# RPIShield.net
KiCad netlist of a schematic drawn in Altium Designer
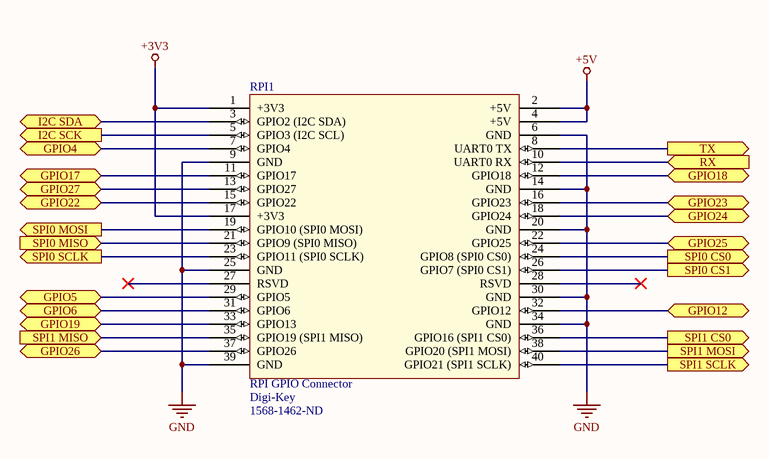
[diagram p0: RPIShield.SchDoc]

(export (version "E")
  (design (tool "Eeschema 10.0.6"))
  (components
    (comp (ref "RPI1")
      (value "RPI GPIO Connector")
      (footprint "rpi")
      (description "GPIO Header for Raspberry Pi A+/B+/Pi 2/Pi 3 - 2x20")
      (fields
        (field (name "MANUFACTURER") "SparkFun Electronics")
        (field (name "MANUFACTURER PART NUMBER") "PRT-14017")
        (field (name "SUPPLIER 1") "Digi-Key")
        (field (name "SUPPLIER PART NUMBER 1") "1568-1462-ND")
      )
      (libsource (lib "rpi") (part "rpi connector"))
    )
  )
  (nets
    (net (code "1") (name "+3V3") (class "Default")
      (node (ref "RPI1") (pin "1") (pinfunction "+3V3_1") (pintype "power_in"))
      (node (ref "RPI1") (pin "17") (pinfunction "+3V3_17") (pintype "power_in"))
    )
    (net (code "2") (name "+5V") (class "Default")
      (node (ref "RPI1") (pin "2") (pinfunction "+5V_2") (pintype "power_in"))
      (node (ref "RPI1") (pin "4") (pinfunction "+5V_4") (pintype "power_in"))
    )
    (net (code "3") (name "/GPIO4") (class "Default")
      (node (ref "RPI1") (pin "7") (pinfunction "GPIO4_7") (pintype "bidirectional"))
    )
    (net (code "4") (name "/GPIO5") (class "Default")
      (node (ref "RPI1") (pin "29") (pinfunction "GPIO5_29") (pintype "bidirectional"))
    )
    (net (code "5") (name "/GPIO6") (class "Default")
      (node (ref "RPI1") (pin "31") (pinfunction "GPIO6_31") (pintype "bidirectional"))
    )
    (net (code "6") (name "/GPIO12") (class "Default")
      (node (ref "RPI1") (pin "32") (pinfunction "GPIO12_32") (pintype "bidirectional"))
    )
    (net (code "7") (name "/GPIO17") (class "Default")
      (node (ref "RPI1") (pin "11") (pinfunction "GPIO17_11") (pintype "bidirectional"))
    )
    (net (code "8") (name "/GPIO18") (class "Default")
      (node (ref "RPI1") (pin "12") (pinfunction "GPIO18_12") (pintype "bidirectional"))
    )
    (net (code "9") (name "/GPIO19") (class "Default")
      (node (ref "RPI1") (pin "33") (pinfunction "GPIO13_33") (pintype "bidirectional"))
    )
    (net (code "10") (name "/GPIO22") (class "Default")
      (node (ref "RPI1") (pin "15") (pinfunction "GPIO22_15") (pintype "bidirectional"))
    )
    (net (code "11") (name "/GPIO23") (class "Default")
      (node (ref "RPI1") (pin "16") (pinfunction "GPIO23_16") (pintype "bidirectional"))
    )
    (net (code "12") (name "/GPIO24") (class "Default")
      (node (ref "RPI1") (pin "18") (pinfunction "GPIO24_18") (pintype "bidirectional"))
    )
    (net (code "13") (name "/GPIO25") (class "Default")
      (node (ref "RPI1") (pin "22") (pinfunction "GPIO25_22") (pintype "bidirectional"))
    )
    (net (code "14") (name "/GPIO26") (class "Default")
      (node (ref "RPI1") (pin "37") (pinfunction "GPIO26_37") (pintype "bidirectional"))
    )
    (net (code "15") (name "/GPIO27") (class "Default")
      (node (ref "RPI1") (pin "13") (pinfunction "GPIO27_13") (pintype "bidirectional"))
    )
    (net (code "16") (name "/I2C SCK") (class "Default")
      (node (ref "RPI1") (pin "5") (pinfunction "GPIO3_(I2C_SCL)_5") (pintype "bidirectional"))
    )
    (net (code "17") (name "/I2C SDA") (class "Default")
      (node (ref "RPI1") (pin "3") (pinfunction "GPIO2_(I2C_SDA)_3") (pintype "bidirectional"))
    )
    (net (code "18") (name "/RX") (class "Default")
      (node (ref "RPI1") (pin "10") (pinfunction "UART0_RX_10") (pintype "bidirectional"))
    )
    (net (code "19") (name "/SPI0 CS0") (class "Default")
      (node (ref "RPI1") (pin "24") (pinfunction "GPIO8_(SPI0_CS0)_24") (pintype "bidirectional"))
    )
    (net (code "20") (name "/SPI0 CS1") (class "Default")
      (node (ref "RPI1") (pin "26") (pinfunction "GPIO7_(SPI0_CS1)_26") (pintype "bidirectional"))
    )
    (net (code "21") (name "/SPI0 MISO") (class "Default")
      (node (ref "RPI1") (pin "21") (pinfunction "GPIO9_(SPI0_MISO)_21") (pintype "bidirectional"))
    )
    (net (code "22") (name "/SPI0 MOSI") (class "Default")
      (node (ref "RPI1") (pin "19") (pinfunction "GPIO10_(SPI0_MOSI)_19") (pintype "bidirectional"))
    )
    (net (code "23") (name "/SPI0 SCLK") (class "Default")
      (node (ref "RPI1") (pin "23") (pinfunction "GPIO11_(SPI0_SCLK)_23") (pintype "bidirectional"))
    )
    (net (code "24") (name "/SPI1 CS0") (class "Default")
      (node (ref "RPI1") (pin "36") (pinfunction "GPIO16_(SPI1_CS0)_36") (pintype "bidirectional"))
    )
    (net (code "25") (name "/SPI1 MISO") (class "Default")
      (node (ref "RPI1") (pin "35") (pinfunction "GPIO19_(SPI1_MISO)_35") (pintype "bidirectional"))
    )
    (net (code "26") (name "/SPI1 MOSI") (class "Default")
      (node (ref "RPI1") (pin "38") (pinfunction "GPIO20_(SPI1_MOSI)_38") (pintype "bidirectional"))
    )
    (net (code "27") (name "/SPI1 SCLK") (class "Default")
      (node (ref "RPI1") (pin "40") (pinfunction "GPIO21_(SPI1_SCLK)_40") (pintype "bidirectional"))
    )
    (net (code "28") (name "/TX") (class "Default")
      (node (ref "RPI1") (pin "8") (pinfunction "UART0_TX_8") (pintype "bidirectional"))
    )
    (net (code "29") (name "GND") (class "Default")
      (node (ref "RPI1") (pin "14") (pinfunction "GND_14") (pintype "power_in"))
      (node (ref "RPI1") (pin "20") (pinfunction "GND_20") (pintype "power_in"))
      (node (ref "RPI1") (pin "25") (pinfunction "GND_25") (pintype "power_in"))
      (node (ref "RPI1") (pin "30") (pinfunction "GND_30") (pintype "power_in"))
      (node (ref "RPI1") (pin "34") (pinfunction "GND_34") (pintype "passive"))
      (node (ref "RPI1") (pin "39") (pinfunction "GND_39") (pintype "power_in"))
      (node (ref "RPI1") (pin "6") (pinfunction "GND_6") (pintype "power_in"))
      (node (ref "RPI1") (pin "9") (pinfunction "GND_9") (pintype "power_in"))
    )
    (net (code "30") (name "unconnected-(RPI1-RSVD-Pad27)") (class "Default")
      (node (ref "RPI1") (pin "27") (pinfunction "RSVD_27") (pintype "passive+no_connect"))
    )
    (net (code "31") (name "unconnected-(RPI1-RSVD-Pad28)") (class "Default")
      (node (ref "RPI1") (pin "28") (pinfunction "RSVD_28") (pintype "passive+no_connect"))
    )
  )
)
